# GPS.net
KiCad netlist of a schematic drawn in Altium Designer
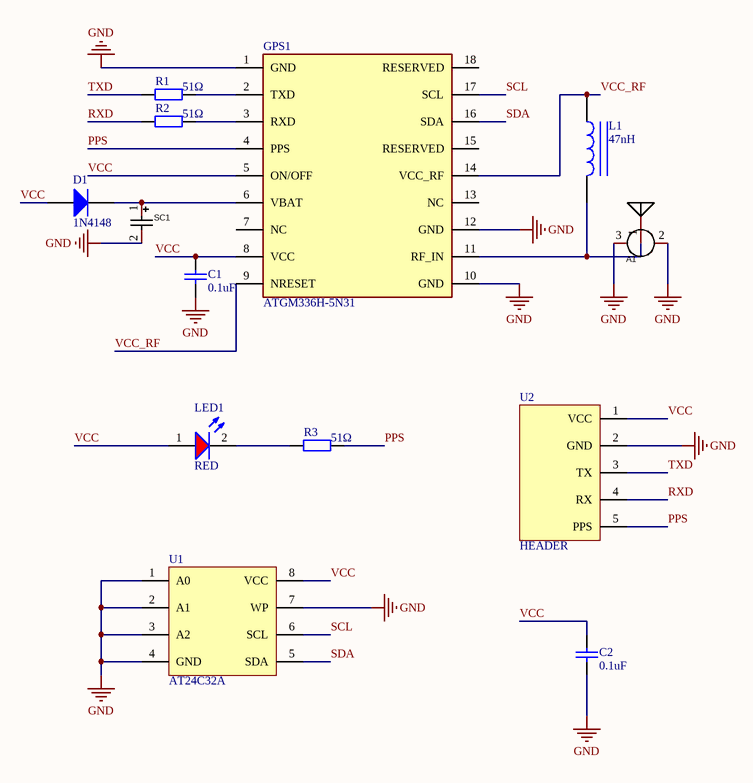
[diagram p0: GPS.SchDoc]

(export (version "E")
  (design (tool "Eeschema 10.0.6"))
  (components
    (comp (ref "A1")
      (value "IPEX1-TXZ")
      (footprint "ipex1")
      (fields (field (name "MANUFACTURER") "SHOU HAN(首韩)") (field (name "MANUFACTURER PART") "IPEX1-TXZ 142"))
      (libsource (lib "PCB_sch") (part "IPEX1-TXZ"))
    )
    (comp (ref "C1")
      (value "0.1uF")
      (footprint "0603_C")
      (description "capacitance")
      (libsource (lib "PCB_sch") (part "0603C"))
    )
    (comp (ref "C2")
      (value "0.1uF")
      (footprint "0603_C")
      (description "capacitance")
      (libsource (lib "PCB_sch") (part "0603C"))
    )
    (comp (ref "D1")
      (value "1N4148")
      (footprint "1N4148")
      (description "diode")
      (libsource (lib "PCB_sch") (part "1N4148"))
    )
    (comp (ref "GPS1")
      (value "ATGM336H-5N31")
      (footprint "ATGM336H-5N-31")
      (description "GSM & GPRS & GPS Modules 9.7X10.1mm RoHS")
      (libsource (lib "PCB_sch") (part "ATGM336H-5N31"))
    )
    (comp (ref "L1")
      (value "47nH")
      (footprint "0603_L")
      (description "inductance")
      (libsource (lib "PCB_sch") (part "0603L"))
    )
    (comp (ref "LED1")
      (value "RED")
      (footprint "LED0603")
      (description "LED")
      (libsource (lib "PCB_sch") (part "LED_RED_1"))
    )
    (comp (ref "R1")
      (value "51Ω")
      (footprint "0603_R")
      (description "resistance")
      (libsource (lib "PCB_sch") (part "0603R"))
    )
    (comp (ref "R2")
      (value "51Ω")
      (footprint "0603_R")
      (description "resistance")
      (libsource (lib "PCB_sch") (part "0603R"))
    )
    (comp (ref "R3")
      (value "51Ω")
      (footprint "0603_R")
      (description "resistance")
      (libsource (lib "PCB_sch") (part "0603R"))
    )
    (comp (ref "SC1")
      (value "XH414HG-IV01E_C38065")
      (footprint "XH414HG")
      (description "super capicator")
      (fields (field (name "MANUFACTURER") "ABLIC(艾普凌科)") (field (name "MANUFACTURER PART") "XH414HG-IV01E"))
      (libsource (lib "PCB_sch") (part "XH414HG"))
    )
    (comp (ref "U1") (value "AT24C32A") (footprint "AT24C32A") (libsource (lib "PCB_sch") (part "AT24C32A")))
    (comp (ref "U2") (value "HEADER") (footprint "HEADER") (libsource (lib "PCB_sch") (part "HEADER")))
  )
  (nets
    (net (code "1") (name "/PPS") (class "Default")
      (node (ref "GPS1") (pin "4") (pinfunction "PPS_4") (pintype "passive"))
      (node (ref "R3") (pin "2") (pinfunction "2_2") (pintype "passive"))
      (node (ref "U2") (pin "5") (pinfunction "PPS_5") (pintype "passive"))
    )
    (net (code "2") (name "/RXD") (class "Default")
      (node (ref "R2") (pin "1") (pinfunction "1_1") (pintype "passive"))
      (node (ref "U2") (pin "4") (pinfunction "RX_4") (pintype "passive"))
    )
    (net (code "3") (name "/SCL") (class "Default")
      (node (ref "GPS1") (pin "17") (pinfunction "SCL_17") (pintype "passive"))
      (node (ref "U1") (pin "6") (pinfunction "SCL_6") (pintype "passive"))
    )
    (net (code "4") (name "/SDA") (class "Default")
      (node (ref "GPS1") (pin "16") (pinfunction "SDA_16") (pintype "passive"))
      (node (ref "U1") (pin "5") (pinfunction "SDA_5") (pintype "passive"))
    )
    (net (code "5") (name "/TXD") (class "Default")
      (node (ref "R1") (pin "1") (pinfunction "1_1") (pintype "passive"))
      (node (ref "U2") (pin "3") (pinfunction "TX_3") (pintype "passive"))
    )
    (net (code "6") (name "/VCC") (class "Default")
      (node (ref "C1") (pin "2") (pinfunction "2_2") (pintype "passive"))
      (node (ref "C2") (pin "2") (pinfunction "2_2") (pintype "passive"))
      (node (ref "D1") (pin "1") (pinfunction "A_1") (pintype "passive"))
      (node (ref "GPS1") (pin "5") (pinfunction "ON/OFF_5") (pintype "passive"))
      (node (ref "GPS1") (pin "8") (pinfunction "VCC_8") (pintype "passive"))
      (node (ref "LED1") (pin "1") (pinfunction "1_1") (pintype "passive"))
      (node (ref "U1") (pin "8") (pinfunction "VCC_8") (pintype "passive"))
      (node (ref "U2") (pin "1") (pinfunction "VCC_1") (pintype "passive"))
    )
    (net (code "7") (name "/VCC_RF") (class "Default")
      (node (ref "GPS1") (pin "14") (pinfunction "VCC_RF_14") (pintype "passive"))
      (node (ref "GPS1") (pin "9") (pinfunction "NRESET_9") (pintype "passive"))
      (node (ref "L1") (pin "1") (pinfunction "1_1") (pintype "passive"))
    )
    (net (code "8") (name "GND") (class "Default")
      (node (ref "A1") (pin "2") (pinfunction "2_2") (pintype "passive"))
      (node (ref "A1") (pin "3") (pinfunction "3_3") (pintype "passive"))
      (node (ref "C1") (pin "1") (pinfunction "1_1") (pintype "passive"))
      (node (ref "C2") (pin "1") (pinfunction "1_1") (pintype "passive"))
      (node (ref "GPS1") (pin "1") (pinfunction "GND_1") (pintype "passive"))
      (node (ref "GPS1") (pin "10") (pinfunction "GND_10") (pintype "passive"))
      (node (ref "GPS1") (pin "12") (pinfunction "GND_12") (pintype "passive"))
      (node (ref "SC1") (pin "2") (pinfunction "2_2") (pintype "passive"))
      (node (ref "U1") (pin "1") (pinfunction "A0_1") (pintype "passive"))
      (node (ref "U1") (pin "2") (pinfunction "A1_2") (pintype "passive"))
      (node (ref "U1") (pin "3") (pinfunction "A2_3") (pintype "passive"))
      (node (ref "U1") (pin "4") (pinfunction "GND_4") (pintype "passive"))
      (node (ref "U1") (pin "7") (pinfunction "WP_7") (pintype "passive"))
      (node (ref "U2") (pin "2") (pinfunction "GND_2") (pintype "passive"))
    )
    (net (code "9") (name "Net-(D1-K)") (class "Default")
      (node (ref "D1") (pin "2") (pinfunction "K_2") (pintype "passive"))
      (node (ref "GPS1") (pin "6") (pinfunction "VBAT_6") (pintype "passive"))
      (node (ref "SC1") (pin "1") (pinfunction "1_1") (pintype "passive"))
    )
    (net (code "10") (name "Net-(GPS1-RF_IN)") (class "Default")
      (node (ref "A1") (pin "1") (pinfunction "1_1") (pintype "passive"))
      (node (ref "GPS1") (pin "11") (pinfunction "RF_IN_11") (pintype "passive"))
      (node (ref "L1") (pin "2") (pinfunction "2_2") (pintype "passive"))
    )
    (net (code "11") (name "Net-(GPS1-RXD)") (class "Default")
      (node (ref "GPS1") (pin "3") (pinfunction "RXD_3") (pintype "passive"))
      (node (ref "R2") (pin "2") (pinfunction "2_2") (pintype "passive"))
    )
    (net (code "12") (name "Net-(GPS1-TXD)") (class "Default")
      (node (ref "GPS1") (pin "2") (pinfunction "TXD_2") (pintype "passive"))
      (node (ref "R1") (pin "2") (pinfunction "2_2") (pintype "passive"))
    )
    (net (code "13") (name "Net-(LED1-Pad2)") (class "Default")
      (node (ref "LED1") (pin "2") (pinfunction "2_2") (pintype "passive"))
      (node (ref "R3") (pin "1") (pinfunction "1_1") (pintype "passive"))
    )
    (net (code "14") (name "unconnected-(GPS1-NC-Pad7)") (class "Default")
      (node (ref "GPS1") (pin "7") (pinfunction "NC_7") (pintype "passive"))
    )
    (net (code "15") (name "unconnected-(GPS1-NC-Pad13)") (class "Default")
      (node (ref "GPS1") (pin "13") (pinfunction "NC_13") (pintype "passive"))
    )
    (net (code "16") (name "unconnected-(GPS1-RESERVED-Pad15)") (class "Default")
      (node (ref "GPS1") (pin "15") (pinfunction "RESERVED_15") (pintype "passive"))
    )
    (net (code "17") (name "unconnected-(GPS1-RESERVED-Pad18)") (class "Default")
      (node (ref "GPS1") (pin "18") (pinfunction "RESERVED_18") (pintype "passive"))
    )
  )
)
